# LED-bas.net
KiCad netlist of a schematic drawn in EAGLE
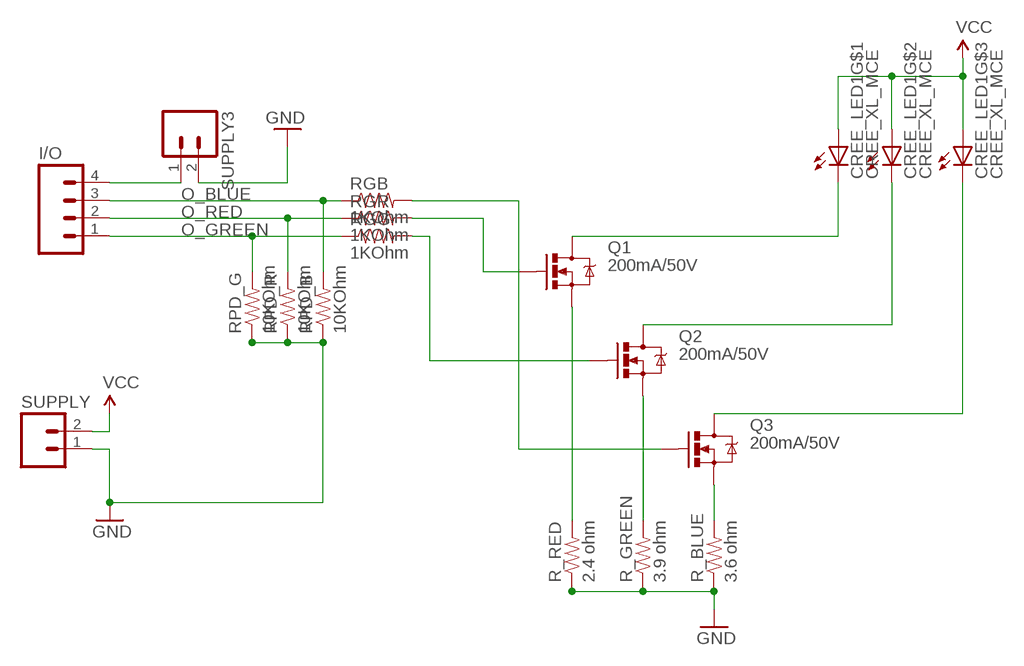
[diagram p0: schematic, sheet 1]

(export (version "E")
  (design (tool "Eeschema 10.0.6"))
  (components
    (comp (ref "CREE_LED1")
      (value "CREE_XL_MCE")
      (footprint "eagle-import:CREE_XL_MCE")
      (libsource (lib "eagle-import") (part "CREE_XL_MCE"))
    )
    (comp (ref "I/O")
      (value "M04NO_SILK_ALL_ROUND")
      (footprint "eagle-import:1X04_NO_SILK_ALL_ROUND")
      (libsource (lib "eagle-import") (part "M04NO_SILK_ALL_ROUND"))
    )
    (comp (ref "Q1")
      (value "200mA/50V")
      (footprint "eagle-import:SOT23-3")
      (libsource (lib "eagle-import") (part "MOSFET-NCHANNELBSS138"))
    )
    (comp (ref "Q2")
      (value "200mA/50V")
      (footprint "eagle-import:SOT23-3")
      (libsource (lib "eagle-import") (part "MOSFET-NCHANNELBSS138"))
    )
    (comp (ref "Q3")
      (value "200mA/50V")
      (footprint "eagle-import:SOT23-3")
      (libsource (lib "eagle-import") (part "MOSFET-NCHANNELBSS138"))
    )
    (comp (ref "RGB")
      (value "1KOhm")
      (footprint "eagle-import:0805")
      (libsource (lib "eagle-import") (part "RESISTOR0805-RES"))
    )
    (comp (ref "RGG")
      (value "1KOhm")
      (footprint "eagle-import:0805")
      (libsource (lib "eagle-import") (part "RESISTOR0805-RES"))
    )
    (comp (ref "RGR")
      (value "1KOhm")
      (footprint "eagle-import:0805")
      (libsource (lib "eagle-import") (part "RESISTOR0805-RES"))
    )
    (comp (ref "RPD_B")
      (value "10KOhm")
      (footprint "eagle-import:0805")
      (libsource (lib "eagle-import") (part "RESISTOR0805-RES"))
    )
    (comp (ref "RPD_G")
      (value "10KOhm")
      (footprint "eagle-import:0805")
      (libsource (lib "eagle-import") (part "RESISTOR0805-RES"))
    )
    (comp (ref "RPD_R")
      (value "10KOhm")
      (footprint "eagle-import:0805")
      (libsource (lib "eagle-import") (part "RESISTOR0805-RES"))
    )
    (comp (ref "R_BLUE")
      (value "3.6 ohm")
      (footprint "eagle-import:0805")
      (libsource (lib "eagle-import") (part "RESISTOR0805-RES"))
    )
    (comp (ref "R_GREEN")
      (value "3.9 ohm")
      (footprint "eagle-import:0805")
      (libsource (lib "eagle-import") (part "RESISTOR0805-RES"))
    )
    (comp (ref "R_RED")
      (value "2.4 ohm")
      (footprint "eagle-import:0805")
      (libsource (lib "eagle-import") (part "RESISTOR0805-RES"))
    )
    (comp (ref "SUPPLY")
      (value "M021X02_NO_SILK")
      (footprint "eagle-import:1X02_NO_SILK")
      (libsource (lib "eagle-import") (part "M021X02_NO_SILK"))
    )
    (comp (ref "SUPPLY3")
      (value "M021X02_NO_SILK")
      (footprint "eagle-import:1X02_NO_SILK")
      (libsource (lib "eagle-import") (part "M021X02_NO_SILK"))
    )
  )
  (nets
    (net (code "1") (name "/O_BLUE") (class "Default")
      (node (ref "I/O") (pin "3") (pinfunction "3_3") (pintype "passive"))
      (node (ref "RGB") (pin "1") (pinfunction "1_1") (pintype "passive"))
      (node (ref "RPD_B") (pin "2") (pinfunction "2_2") (pintype "passive"))
    )
    (net (code "2") (name "/O_GREEN") (class "Default")
      (node (ref "I/O") (pin "1") (pinfunction "1_1") (pintype "passive"))
      (node (ref "RGG") (pin "1") (pinfunction "1_1") (pintype "passive"))
      (node (ref "RPD_G") (pin "2") (pinfunction "2_2") (pintype "passive"))
    )
    (net (code "3") (name "/O_RED") (class "Default")
      (node (ref "I/O") (pin "2") (pinfunction "2_2") (pintype "passive"))
      (node (ref "RGR") (pin "1") (pinfunction "1_1") (pintype "passive"))
      (node (ref "RPD_R") (pin "2") (pinfunction "2_2") (pintype "passive"))
    )
    (net (code "4") (name "GND") (class "Default")
      (node (ref "RPD_B") (pin "1") (pinfunction "1_1") (pintype "passive"))
      (node (ref "RPD_G") (pin "1") (pinfunction "1_1") (pintype "passive"))
      (node (ref "RPD_R") (pin "1") (pinfunction "1_1") (pintype "passive"))
      (node (ref "R_BLUE") (pin "1") (pinfunction "1_1") (pintype "passive"))
      (node (ref "R_GREEN") (pin "1") (pinfunction "1_1") (pintype "passive"))
      (node (ref "R_RED") (pin "1") (pinfunction "1_1") (pintype "passive"))
      (node (ref "SUPPLY") (pin "1") (pinfunction "1_1") (pintype "passive"))
      (node (ref "SUPPLY3") (pin "2") (pinfunction "2_2") (pintype "passive"))
    )
    (net (code "5") (name "Net-(CREE_LED1A-C)") (class "Default")
      (node (ref "CREE_LED1") (pin "8") (pinfunction "C_8") (pintype "passive"))
      (node (ref "Q1") (pin "3") (pinfunction "D_3") (pintype "passive"))
    )
    (net (code "6") (name "Net-(CREE_LED1B-C)") (class "Default")
      (node (ref "CREE_LED1") (pin "7") (pinfunction "C_7") (pintype "passive"))
      (node (ref "Q2") (pin "3") (pinfunction "D_3") (pintype "passive"))
    )
    (net (code "7") (name "Net-(CREE_LED1C-C)") (class "Default")
      (node (ref "CREE_LED1") (pin "6") (pinfunction "C_6") (pintype "passive"))
      (node (ref "Q3") (pin "3") (pinfunction "D_3") (pintype "passive"))
    )
    (net (code "8") (name "Net-(I/O-Pad4)") (class "Default")
      (node (ref "I/O") (pin "4") (pinfunction "4_4") (pintype "passive"))
      (node (ref "SUPPLY3") (pin "1") (pinfunction "1_1") (pintype "passive"))
    )
    (net (code "9") (name "Net-(Q1-G)") (class "Default")
      (node (ref "Q1") (pin "1") (pinfunction "G_1") (pintype "passive"))
      (node (ref "RGR") (pin "2") (pinfunction "2_2") (pintype "passive"))
    )
    (net (code "10") (name "Net-(Q1-S)") (class "Default")
      (node (ref "Q1") (pin "2") (pinfunction "S_2") (pintype "passive"))
      (node (ref "R_RED") (pin "2") (pinfunction "2_2") (pintype "passive"))
    )
    (net (code "11") (name "Net-(Q2-G)") (class "Default")
      (node (ref "Q2") (pin "1") (pinfunction "G_1") (pintype "passive"))
      (node (ref "RGG") (pin "2") (pinfunction "2_2") (pintype "passive"))
    )
    (net (code "12") (name "Net-(Q2-S)") (class "Default")
      (node (ref "Q2") (pin "2") (pinfunction "S_2") (pintype "passive"))
      (node (ref "R_GREEN") (pin "2") (pinfunction "2_2") (pintype "passive"))
    )
    (net (code "13") (name "Net-(Q3-G)") (class "Default")
      (node (ref "Q3") (pin "1") (pinfunction "G_1") (pintype "passive"))
      (node (ref "RGB") (pin "2") (pinfunction "2_2") (pintype "passive"))
    )
    (net (code "14") (name "Net-(Q3-S)") (class "Default")
      (node (ref "Q3") (pin "2") (pinfunction "S_2") (pintype "passive"))
      (node (ref "R_BLUE") (pin "2") (pinfunction "2_2") (pintype "passive"))
    )
    (net (code "15") (name "VCC") (class "Default")
      (node (ref "CREE_LED1") (pin "1") (pinfunction "A_1") (pintype "passive"))
      (node (ref "CREE_LED1") (pin "2") (pinfunction "A_2") (pintype "passive"))
      (node (ref "CREE_LED1") (pin "3") (pinfunction "A_3") (pintype "passive"))
      (node (ref "SUPPLY") (pin "2") (pinfunction "2_2") (pintype "passive"))
    )
  )
)
